# ESP8266_BREAKOUT.net
KiCad netlist of a schematic drawn in EAGLE
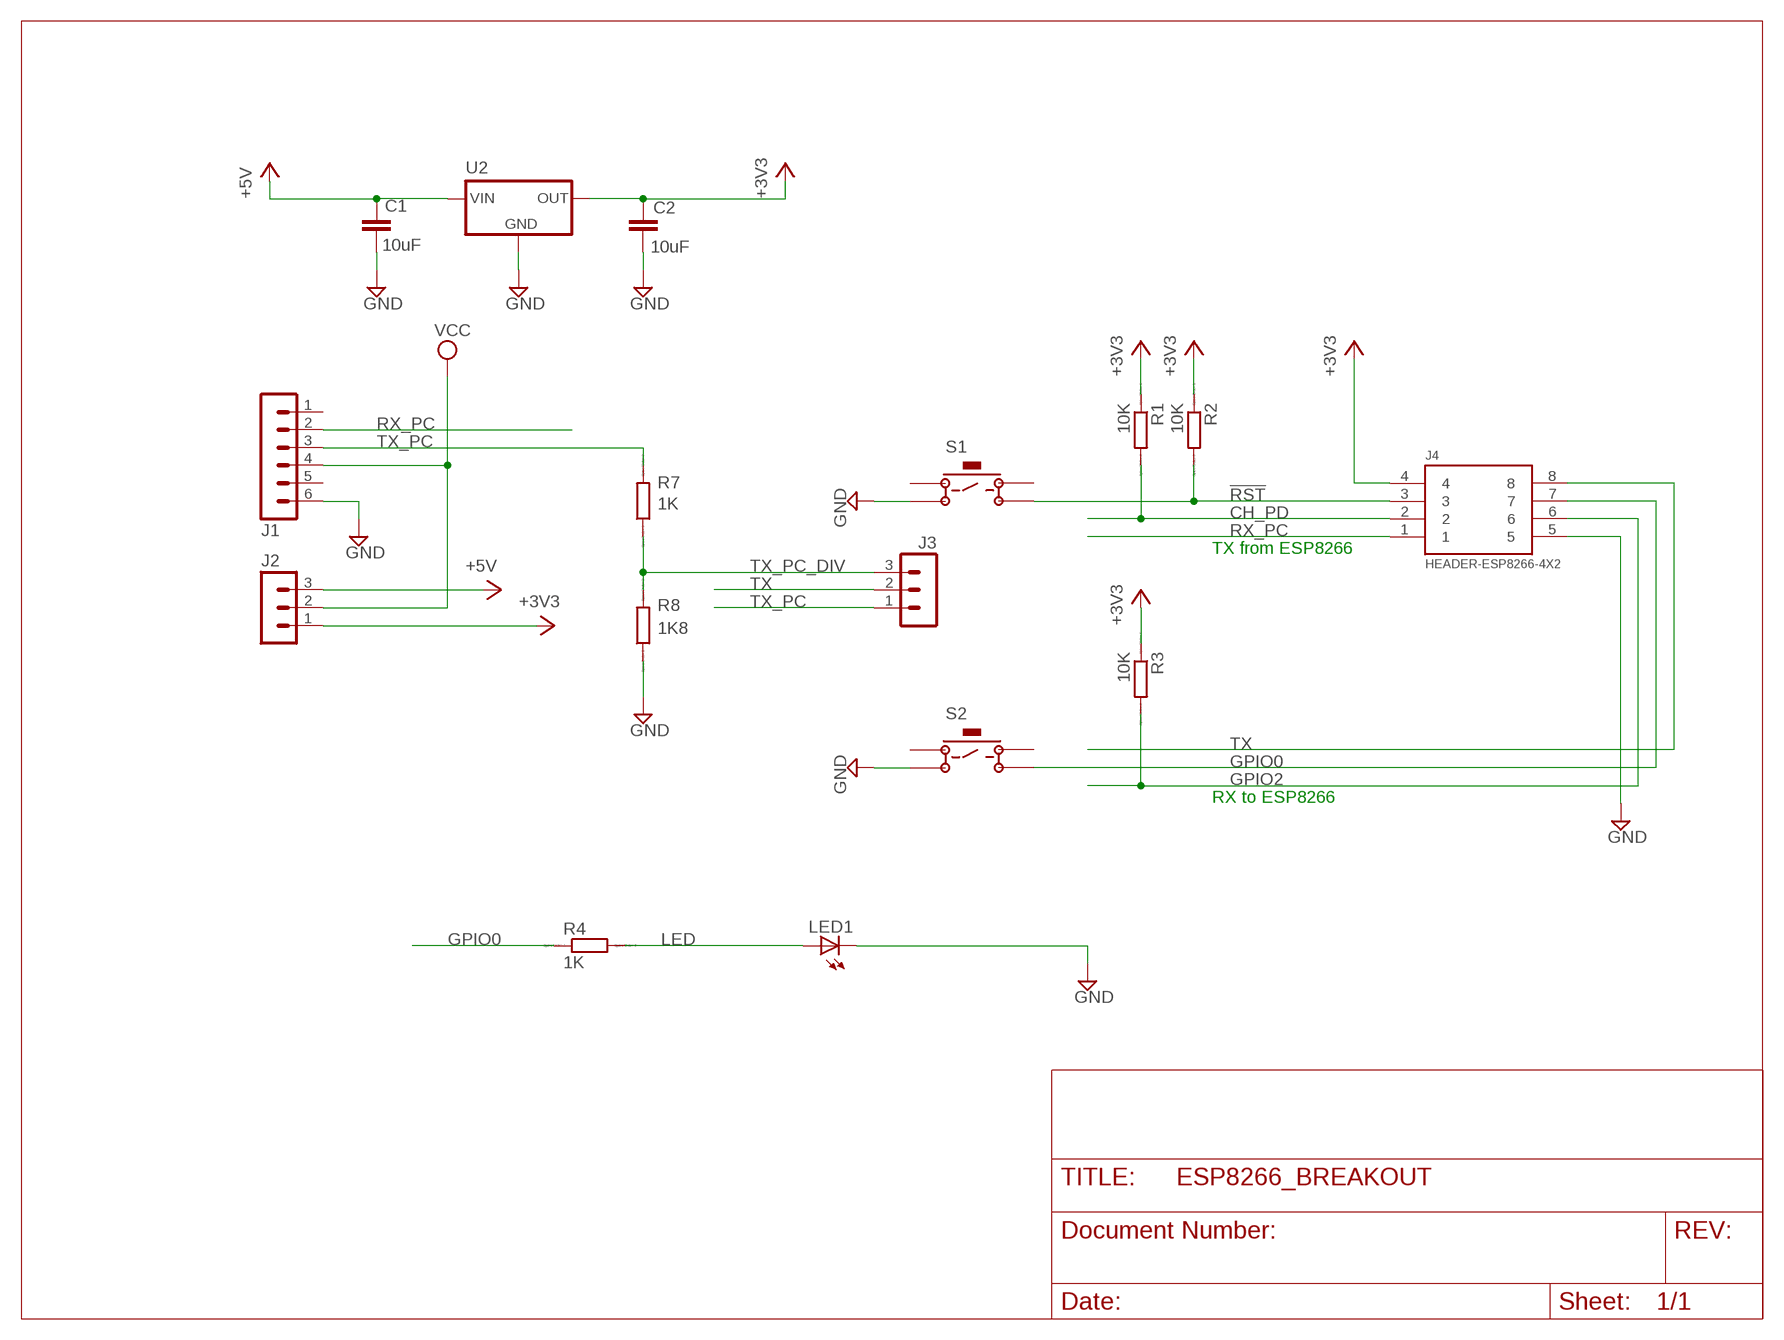
[diagram p0: schematic, sheet 1]

(export (version "E")
  (design (tool "Eeschema 10.0.6"))
  (components
    (comp (ref "C1")
      (value "10uF")
      (footprint "eagle-import:C5B2.5")
      (libsource (lib "eagle-import") (part "C5/2.5"))
    )
    (comp (ref "C2")
      (value "10uF")
      (footprint "eagle-import:C5B2.5")
      (libsource (lib "eagle-import") (part "C5/2.5"))
    )
    (comp (ref "J1")
      (value "MA06-1")
      (footprint "eagle-import:MA06-1")
      (libsource (lib "eagle-import") (part "MA06-1"))
    )
    (comp (ref "J2")
      (value "MA03-1")
      (footprint "eagle-import:MA03-1")
      (libsource (lib "eagle-import") (part "MA03-1"))
    )
    (comp (ref "J3")
      (value "MA03-1")
      (footprint "eagle-import:MA03-1")
      (libsource (lib "eagle-import") (part "MA03-1"))
    )
    (comp (ref "J4")
      (value "HEADER-ESP8266-4X2")
      (footprint "eagle-import:HEADER-4X2-A")
      (libsource (lib "eagle-import") (part "HEADER-ESP8266-4X2"))
    )
    (comp (ref "LED1")
      (value "LED5MM")
      (footprint "eagle-import:LED5MM")
      (libsource (lib "eagle-import") (part "LED5MM"))
    )
    (comp (ref "R1")
      (value "10K")
      (footprint "eagle-import:0204_7")
      (libsource (lib "eagle-import") (part "R-EU_0204_7"))
    )
    (comp (ref "R2")
      (value "10K")
      (footprint "eagle-import:0204_7")
      (libsource (lib "eagle-import") (part "R-EU_0204_7"))
    )
    (comp (ref "R3")
      (value "10K")
      (footprint "eagle-import:0204_7")
      (libsource (lib "eagle-import") (part "R-EU_0204_7"))
    )
    (comp (ref "R4")
      (value "1K")
      (footprint "eagle-import:0204_7")
      (libsource (lib "eagle-import") (part "R-EU_0204_7"))
    )
    (comp (ref "R7")
      (value "1K")
      (footprint "eagle-import:0204_7")
      (libsource (lib "eagle-import") (part "R-EU_0204_7"))
    )
    (comp (ref "R8")
      (value "1K8")
      (footprint "eagle-import:0204_7")
      (libsource (lib "eagle-import") (part "R-EU_0204_7"))
    )
    (comp (ref "S1")
      (value "1825910-6-SPST-NOPB-4P")
      (footprint "eagle-import:SW-NOPB-4")
      (libsource (lib "eagle-import") (part "1825910-6-SPST-NOPB-4P"))
    )
    (comp (ref "S2")
      (value "1825910-6-SPST-NOPB-4P")
      (footprint "eagle-import:SW-NOPB-4")
      (libsource (lib "eagle-import") (part "1825910-6-SPST-NOPB-4P"))
    )
    (comp (ref "U2")
      (value "LM1117-3V3-T0-220")
      (footprint "eagle-import:TO-220")
      (libsource (lib "eagle-import") (part "LM1117-3V3-T0-220"))
    )
  )
  (nets
    (net (code "1") (name "+3V3") (class "Default")
      (node (ref "C2") (pin "2") (pinfunction "2_2") (pintype "passive"))
      (node (ref "J2") (pin "1") (pinfunction "1_1") (pintype "passive"))
      (node (ref "J4") (pin "4") (pinfunction "4_4") (pintype "bidirectional"))
      (node (ref "R1") (pin "1") (pinfunction "1_1") (pintype "passive"))
      (node (ref "R2") (pin "1") (pinfunction "1_1") (pintype "passive"))
      (node (ref "R3") (pin "1") (pinfunction "1_1") (pintype "passive"))
      (node (ref "U2") (pin "P$2") (pinfunction "OUT_P$2") (pintype "passive"))
    )
    (net (code "2") (name "+5V") (class "Default")
      (node (ref "C1") (pin "2") (pinfunction "2_2") (pintype "passive"))
      (node (ref "J2") (pin "3") (pinfunction "3_3") (pintype "passive"))
      (node (ref "U2") (pin "P$3") (pinfunction "IN_P$3") (pintype "input"))
    )
    (net (code "3") (name "/CH_PD") (class "Default")
      (node (ref "J4") (pin "2") (pinfunction "2_2") (pintype "bidirectional"))
      (node (ref "R1") (pin "2") (pinfunction "2_2") (pintype "passive"))
    )
    (net (code "4") (name "/GPIO0") (class "Default")
      (node (ref "J4") (pin "7") (pinfunction "7_7") (pintype "bidirectional"))
      (node (ref "R4") (pin "1") (pinfunction "1_1") (pintype "passive"))
      (node (ref "S2") (pin "4") (pinfunction "4_4") (pintype "bidirectional"))
    )
    (net (code "5") (name "/GPIO2") (class "Default")
      (node (ref "J4") (pin "6") (pinfunction "6_6") (pintype "bidirectional"))
      (node (ref "R3") (pin "2") (pinfunction "2_2") (pintype "passive"))
    )
    (net (code "6") (name "/LED") (class "Default")
      (node (ref "LED1") (pin "A") (pinfunction "A_A") (pintype "passive"))
      (node (ref "R4") (pin "2") (pinfunction "2_2") (pintype "passive"))
    )
    (net (code "7") (name "/RX_PC") (class "Default")
      (node (ref "J1") (pin "2") (pinfunction "2_2") (pintype "passive"))
      (node (ref "J4") (pin "1") (pinfunction "1_1") (pintype "bidirectional"))
    )
    (net (code "8") (name "/TX") (class "Default")
      (node (ref "J3") (pin "2") (pinfunction "2_2") (pintype "passive"))
      (node (ref "J4") (pin "8") (pinfunction "8_8") (pintype "bidirectional"))
    )
    (net (code "9") (name "/TX_PC") (class "Default")
      (node (ref "J1") (pin "3") (pinfunction "3_3") (pintype "passive"))
      (node (ref "J3") (pin "1") (pinfunction "1_1") (pintype "passive"))
      (node (ref "R7") (pin "2") (pinfunction "2_2") (pintype "passive"))
    )
    (net (code "10") (name "/TX_PC_DIV") (class "Default")
      (node (ref "J3") (pin "3") (pinfunction "3_3") (pintype "passive"))
      (node (ref "R7") (pin "1") (pinfunction "1_1") (pintype "passive"))
      (node (ref "R8") (pin "2") (pinfunction "2_2") (pintype "passive"))
    )
    (net (code "11") (name "/~{RST}") (class "Default")
      (node (ref "J4") (pin "3") (pinfunction "3_3") (pintype "bidirectional"))
      (node (ref "R2") (pin "2") (pinfunction "2_2") (pintype "passive"))
      (node (ref "S1") (pin "4") (pinfunction "4_4") (pintype "bidirectional"))
    )
    (net (code "12") (name "GND") (class "Default")
      (node (ref "C1") (pin "1") (pinfunction "1_1") (pintype "passive"))
      (node (ref "C2") (pin "1") (pinfunction "1_1") (pintype "passive"))
      (node (ref "J1") (pin "6") (pinfunction "6_6") (pintype "passive"))
      (node (ref "J4") (pin "5") (pinfunction "5_5") (pintype "bidirectional"))
      (node (ref "LED1") (pin "K") (pinfunction "C_K") (pintype "passive"))
      (node (ref "R8") (pin "1") (pinfunction "1_1") (pintype "passive"))
      (node (ref "S1") (pin "2") (pinfunction "2_2") (pintype "bidirectional"))
      (node (ref "S2") (pin "2") (pinfunction "2_2") (pintype "bidirectional"))
      (node (ref "U2") (pin "P$1") (pinfunction "GND_P$1") (pintype "input"))
    )
    (net (code "13") (name "VCC") (class "Default")
      (node (ref "J1") (pin "4") (pinfunction "4_4") (pintype "passive"))
      (node (ref "J2") (pin "2") (pinfunction "2_2") (pintype "passive"))
    )
    (net (code "14") (name "unconnected-(J1-Pad1)") (class "Default")
      (node (ref "J1") (pin "1") (pinfunction "1_1") (pintype "passive"))
    )
    (net (code "15") (name "unconnected-(J1-Pad5)") (class "Default")
      (node (ref "J1") (pin "5") (pinfunction "5_5") (pintype "passive"))
    )
    (net (code "16") (name "unconnected-(S1-Pad1)") (class "Default")
      (node (ref "S1") (pin "1") (pinfunction "1_1") (pintype "bidirectional"))
    )
    (net (code "17") (name "unconnected-(S1-Pad3)") (class "Default")
      (node (ref "S1") (pin "3") (pinfunction "3_3") (pintype "bidirectional"))
    )
    (net (code "18") (name "unconnected-(S2-Pad1)") (class "Default")
      (node (ref "S2") (pin "1") (pinfunction "1_1") (pintype "bidirectional"))
    )
    (net (code "19") (name "unconnected-(S2-Pad3)") (class "Default")
      (node (ref "S2") (pin "3") (pinfunction "3_3") (pintype "bidirectional"))
    )
  )
)
